# gatedriver_trafo_sma_compact_ACDC_SMD.net
KiCad netlist of a schematic drawn in EAGLE
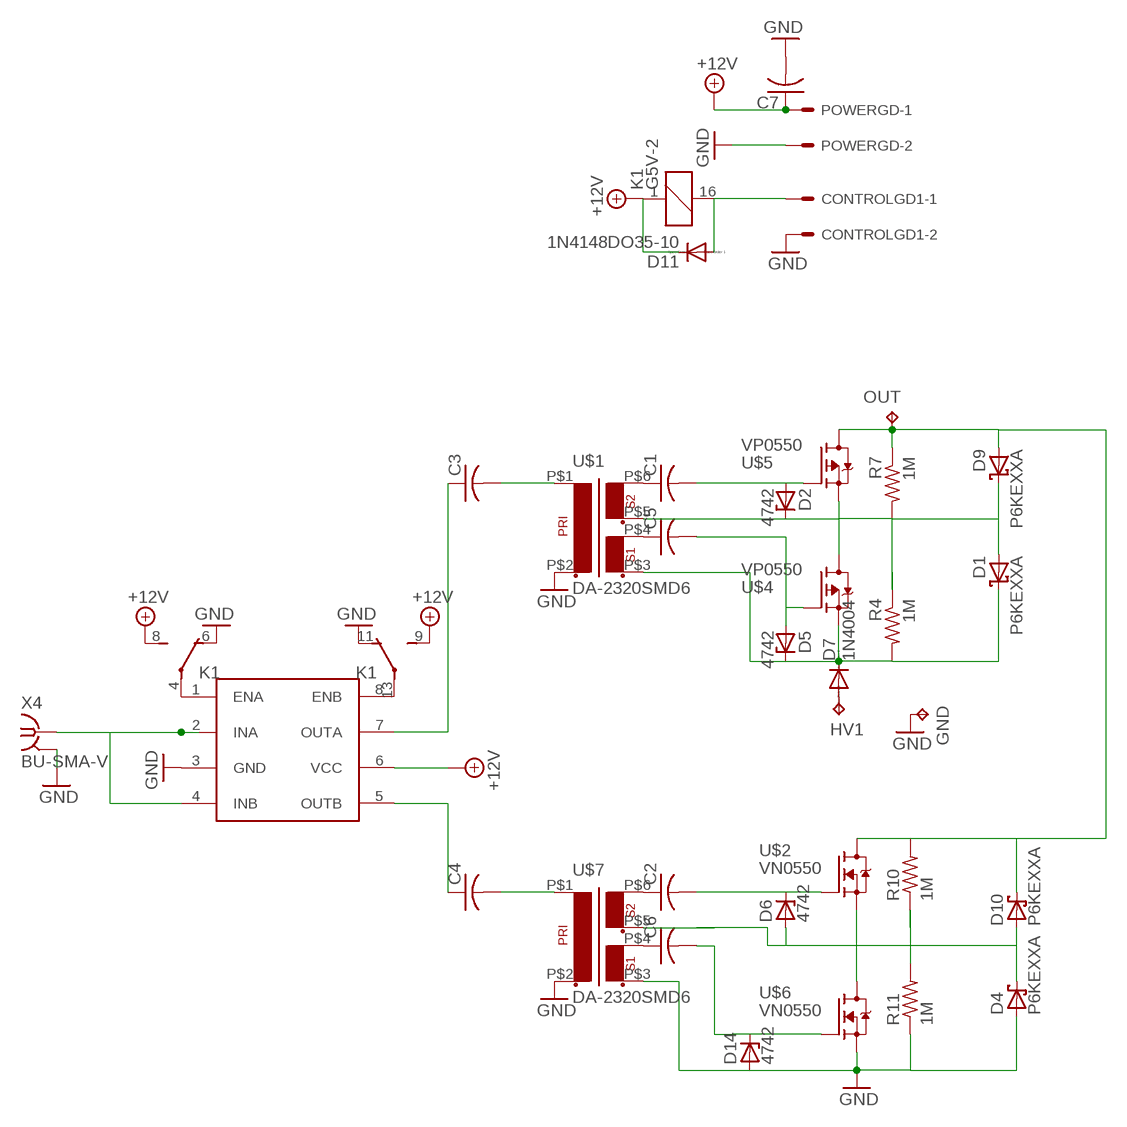
[diagram p0: schematic, sheet 1]

(export (version "E")
  (design (tool "Eeschema 10.0.6"))
  (components
    (comp (ref "C1")
      (value "C-US050-055X075")
      (footprint "eagle-import:C050-055X075")
      (libsource (lib "eagle-import") (part "resistor_C-US050-055X075"))
    )
    (comp (ref "C2")
      (value "C-US050-055X075")
      (footprint "eagle-import:C050-055X075")
      (libsource (lib "eagle-import") (part "resistor_C-US050-055X075"))
    )
    (comp (ref "C3")
      (value "C-US050-055X075")
      (footprint "eagle-import:C050-055X075")
      (libsource (lib "eagle-import") (part "resistor_C-US050-055X075"))
    )
    (comp (ref "C4")
      (value "C-US050-055X075")
      (footprint "eagle-import:C050-055X075")
      (libsource (lib "eagle-import") (part "resistor_C-US050-055X075"))
    )
    (comp (ref "C5")
      (value "C-US050-055X075")
      (footprint "eagle-import:C050-055X075")
      (libsource (lib "eagle-import") (part "resistor_C-US050-055X075"))
    )
    (comp (ref "C6")
      (value "C-US050-055X075")
      (footprint "eagle-import:C050-055X075")
      (libsource (lib "eagle-import") (part "resistor_C-US050-055X075"))
    )
    (comp (ref "C7")
      (value "C-US050-030X075")
      (footprint "eagle-import:C050-030X075")
      (libsource (lib "eagle-import") (part "C-US050-030X075"))
    )
    (comp (ref "CONTROLGD1")
      (value "KK-156-2")
      (footprint "eagle-import:KK-156-2")
      (libsource (lib "eagle-import") (part "KK-156-2"))
    )
    (comp (ref "D1")
      (value "P6KEXXA")
      (footprint "eagle-import:C1702-15")
      (libsource (lib "eagle-import") (part "P6KEXXA"))
    )
    (comp (ref "D2")
      (value "4742")
      (footprint "eagle-import:ZDIO-10")
      (libsource (lib "eagle-import") (part "ZENER-DIODEZD-10"))
    )
    (comp (ref "D4")
      (value "P6KEXXA")
      (footprint "eagle-import:C1702-15")
      (libsource (lib "eagle-import") (part "P6KEXXA"))
    )
    (comp (ref "D5")
      (value "4742")
      (footprint "eagle-import:ZDIO-10")
      (libsource (lib "eagle-import") (part "ZENER-DIODEZD-10"))
    )
    (comp (ref "D6")
      (value "4742")
      (footprint "eagle-import:ZDIO-10")
      (libsource (lib "eagle-import") (part "ZENER-DIODEZD-10"))
    )
    (comp (ref "D7")
      (value "1N4004")
      (footprint "eagle-import:DO41-10")
      (libsource (lib "eagle-import") (part "1N4004"))
    )
    (comp (ref "D9")
      (value "P6KEXXA")
      (footprint "eagle-import:C1702-15")
      (libsource (lib "eagle-import") (part "P6KEXXA"))
    )
    (comp (ref "D10")
      (value "P6KEXXA")
      (footprint "eagle-import:C1702-15")
      (libsource (lib "eagle-import") (part "P6KEXXA"))
    )
    (comp (ref "D11")
      (value "1N4148DO35-10")
      (footprint "eagle-import:DO35-10")
      (libsource (lib "eagle-import") (part "1N4148DO35-10"))
    )
    (comp (ref "D14")
      (value "4742")
      (footprint "eagle-import:ZDIO-10")
      (libsource (lib "eagle-import") (part "ZENER-DIODEZD-10"))
    )
    (comp (ref "GND")
      (value "TPPAD1-20Y")
      (footprint "eagle-import:P1-20Y")
      (libsource (lib "eagle-import") (part "TPPAD1-20Y"))
    )
    (comp (ref "HV1")
      (value "TPPAD1-20Y")
      (footprint "eagle-import:P1-20Y")
      (libsource (lib "eagle-import") (part "TPPAD1-20Y"))
    )
    (comp (ref "K1")
      (value "G5V-2")
      (footprint "eagle-import:G5V-2")
      (fields (field (name "MPN") "G5V-2 5DC"))
      (libsource (lib "eagle-import") (part "G5V-2"))
    )
    (comp (ref "OUT")
      (value "TPPAD1-20Y")
      (footprint "eagle-import:P1-20Y")
      (libsource (lib "eagle-import") (part "TPPAD1-20Y"))
    )
    (comp (ref "POWERGD")
      (value "KK-156-2")
      (footprint "eagle-import:KK-156-2")
      (libsource (lib "eagle-import") (part "KK-156-2"))
    )
    (comp (ref "R4")
      (value "1M")
      (footprint "eagle-import:0207_12")
      (libsource (lib "eagle-import") (part "R-US_0207/12"))
    )
    (comp (ref "R7")
      (value "1M")
      (footprint "eagle-import:0207_12")
      (libsource (lib "eagle-import") (part "R-US_0207/12"))
    )
    (comp (ref "R10")
      (value "1M")
      (footprint "eagle-import:0207_12")
      (libsource (lib "eagle-import") (part "R-US_0207/12"))
    )
    (comp (ref "R11")
      (value "1M")
      (footprint "eagle-import:0207_12")
      (libsource (lib "eagle-import") (part "R-US_0207/12"))
    )
    (comp (ref "U$1")
      (value "DA-2320SMD6")
      (footprint "eagle-import:SMD6")
      (libsource (lib "eagle-import") (part "DA-2320SMD6"))
    )
    (comp (ref "U$2")
      (value "VN0550")
      (footprint "eagle-import:TO92-")
      (libsource (lib "eagle-import") (part "VN0550"))
    )
    (comp (ref "U$3")
      (value "UCC27425")
      (footprint "eagle-import:DIL08")
      (libsource (lib "eagle-import") (part "UCC27425"))
    )
    (comp (ref "U$4")
      (value "VP0550")
      (footprint "eagle-import:TO92-")
      (libsource (lib "eagle-import") (part "VP0550"))
    )
    (comp (ref "U$5")
      (value "VP0550")
      (footprint "eagle-import:TO92-")
      (libsource (lib "eagle-import") (part "VP0550"))
    )
    (comp (ref "U$6")
      (value "VN0550")
      (footprint "eagle-import:TO92-")
      (libsource (lib "eagle-import") (part "VN0550"))
    )
    (comp (ref "U$7")
      (value "DA-2320SMD6")
      (footprint "eagle-import:SMD6")
      (libsource (lib "eagle-import") (part "DA-2320SMD6"))
    )
    (comp (ref "X4")
      (value "BU-SMA-V")
      (footprint "eagle-import:BU-SMA-V")
      (libsource (lib "eagle-import") (part "BU-SMA-V"))
    )
  )
  (nets
    (net (code "1") (name "+12V") (class "Default")
      (node (ref "C7") (pin "1") (pinfunction "1_1") (pintype "passive"))
      (node (ref "D11") (pin "C") (pinfunction "C_C") (pintype "passive"))
      (node (ref "K1") (pin "1") (pinfunction "1_1") (pintype "passive"))
      (node (ref "K1") (pin "8") (pinfunction "S_8") (pintype "passive"))
      (node (ref "K1") (pin "9") (pinfunction "S_9") (pintype "passive"))
      (node (ref "POWERGD") (pin "1") (pinfunction "S_1") (pintype "passive"))
      (node (ref "U$3") (pin "6") (pinfunction "VCC_6") (pintype "bidirectional"))
    )
    (net (code "2") (name "/N$25") (class "Default")
      (node (ref "C2") (pin "2") (pinfunction "2_2") (pintype "passive"))
      (node (ref "D6") (pin "C") (pinfunction "C_C") (pintype "passive"))
      (node (ref "U$2") (pin "2") (pinfunction "G_2") (pintype "passive"))
    )
    (net (code "3") (name "GND") (class "Default")
      (node (ref "C7") (pin "2") (pinfunction "2_2") (pintype "passive"))
      (node (ref "CONTROLGD1") (pin "2") (pinfunction "S_2") (pintype "passive"))
      (node (ref "D14") (pin "A") (pinfunction "A_A") (pintype "passive"))
      (node (ref "D4") (pin "A") (pinfunction "A_A") (pintype "passive"))
      (node (ref "GND") (pin "TP") (pinfunction "TP_TP") (pintype "input"))
      (node (ref "K1") (pin "11") (pinfunction "O_11") (pintype "passive"))
      (node (ref "K1") (pin "6") (pinfunction "O_6") (pintype "passive"))
      (node (ref "POWERGD") (pin "2") (pinfunction "S_2") (pintype "passive"))
      (node (ref "R11") (pin "1") (pinfunction "1_1") (pintype "passive"))
      (node (ref "U$1") (pin "P$2") (pinfunction "2_P$2") (pintype "passive"))
      (node (ref "U$3") (pin "3") (pinfunction "GND_3") (pintype "bidirectional"))
      (node (ref "U$6") (pin "3") (pinfunction "S_3") (pintype "passive"))
      (node (ref "U$7") (pin "P$2") (pinfunction "2_P$2") (pintype "passive"))
      (node (ref "U$7") (pin "P$3") (pinfunction "3_P$3") (pintype "passive"))
      (node (ref "X4") (pin "2") (pinfunction "2_2") (pintype "passive"))
      (node (ref "X4") (pin "3") (pinfunction "2_3") (pintype "passive"))
      (node (ref "X4") (pin "4") (pinfunction "2_4") (pintype "passive"))
      (node (ref "X4") (pin "5") (pinfunction "2_5") (pintype "passive"))
    )
    (net (code "4") (name "Net-(CONTROLGD1A-S)") (class "Default")
      (node (ref "CONTROLGD1") (pin "1") (pinfunction "S_1") (pintype "passive"))
      (node (ref "D11") (pin "A") (pinfunction "A_A") (pintype "passive"))
      (node (ref "K1") (pin "16") (pinfunction "2_16") (pintype "passive"))
    )
    (net (code "5") (name "Net-(D7-PadA)") (class "Default")
      (node (ref "D7") (pin "A") (pinfunction "A_A") (pintype "passive"))
      (node (ref "HV1") (pin "TP") (pinfunction "TP_TP") (pintype "input"))
    )
    (net (code "6") (name "Net-(K1A-P)") (class "Default")
      (node (ref "K1") (pin "4") (pinfunction "P_4") (pintype "passive"))
      (node (ref "U$3") (pin "1") (pinfunction "ENA_1") (pintype "bidirectional"))
    )
    (net (code "7") (name "Net-(K1B-P)") (class "Default")
      (node (ref "K1") (pin "13") (pinfunction "P_13") (pintype "passive"))
      (node (ref "U$3") (pin "8") (pinfunction "ENB_8") (pintype "bidirectional"))
    )
    (net (code "8") (name "Net-(U$1-1)") (class "Default")
      (node (ref "C3") (pin "2") (pinfunction "2_2") (pintype "passive"))
      (node (ref "U$1") (pin "P$1") (pinfunction "1_P$1") (pintype "passive"))
    )
    (net (code "9") (name "Net-(U$1-3)") (class "Default")
      (node (ref "D1") (pin "C") (pinfunction "C_C") (pintype "passive"))
      (node (ref "D5") (pin "C") (pinfunction "C_C") (pintype "passive"))
      (node (ref "D7") (pin "C") (pinfunction "C_C") (pintype "passive"))
      (node (ref "R4") (pin "2") (pinfunction "2_2") (pintype "passive"))
      (node (ref "U$1") (pin "P$3") (pinfunction "3_P$3") (pintype "passive"))
      (node (ref "U$4") (pin "3") (pinfunction "S_3") (pintype "passive"))
    )
    (net (code "10") (name "Net-(U$1-4)") (class "Default")
      (node (ref "C5") (pin "1") (pinfunction "1_1") (pintype "passive"))
      (node (ref "U$1") (pin "P$4") (pinfunction "4_P$4") (pintype "passive"))
    )
    (net (code "11") (name "Net-(U$1-5)") (class "Default")
      (node (ref "D1") (pin "A") (pinfunction "A_A") (pintype "passive"))
      (node (ref "D2") (pin "C") (pinfunction "C_C") (pintype "passive"))
      (node (ref "D9") (pin "C") (pinfunction "C_C") (pintype "passive"))
      (node (ref "R4") (pin "1") (pinfunction "1_1") (pintype "passive"))
      (node (ref "R7") (pin "2") (pinfunction "2_2") (pintype "passive"))
      (node (ref "U$1") (pin "P$5") (pinfunction "5_P$5") (pintype "passive"))
      (node (ref "U$4") (pin "1") (pinfunction "D_1") (pintype "passive"))
      (node (ref "U$5") (pin "3") (pinfunction "S_3") (pintype "passive"))
    )
    (net (code "12") (name "Net-(U$1-6)") (class "Default")
      (node (ref "C1") (pin "1") (pinfunction "1_1") (pintype "passive"))
      (node (ref "U$1") (pin "P$6") (pinfunction "6_P$6") (pintype "passive"))
    )
    (net (code "13") (name "Net-(U$2-D)") (class "Default")
      (node (ref "D10") (pin "C") (pinfunction "C_C") (pintype "passive"))
      (node (ref "D9") (pin "A") (pinfunction "A_A") (pintype "passive"))
      (node (ref "OUT") (pin "TP") (pinfunction "TP_TP") (pintype "input"))
      (node (ref "R10") (pin "2") (pinfunction "2_2") (pintype "passive"))
      (node (ref "R7") (pin "1") (pinfunction "1_1") (pintype "passive"))
      (node (ref "U$2") (pin "1") (pinfunction "D_1") (pintype "passive"))
      (node (ref "U$5") (pin "1") (pinfunction "D_1") (pintype "passive"))
    )
    (net (code "14") (name "Net-(U$2-S)") (class "Default")
      (node (ref "D10") (pin "A") (pinfunction "A_A") (pintype "passive"))
      (node (ref "D4") (pin "C") (pinfunction "C_C") (pintype "passive"))
      (node (ref "D6") (pin "A") (pinfunction "A_A") (pintype "passive"))
      (node (ref "R10") (pin "1") (pinfunction "1_1") (pintype "passive"))
      (node (ref "R11") (pin "2") (pinfunction "2_2") (pintype "passive"))
      (node (ref "U$2") (pin "3") (pinfunction "S_3") (pintype "passive"))
      (node (ref "U$6") (pin "1") (pinfunction "D_1") (pintype "passive"))
    )
    (net (code "15") (name "Net-(U$3-INA)") (class "Default")
      (node (ref "U$3") (pin "2") (pinfunction "INA_2") (pintype "bidirectional"))
      (node (ref "U$3") (pin "4") (pinfunction "INB_4") (pintype "bidirectional"))
      (node (ref "X4") (pin "1") (pinfunction "1_1") (pintype "passive"))
    )
    (net (code "16") (name "Net-(U$3-OUTA)") (class "Default")
      (node (ref "C3") (pin "1") (pinfunction "1_1") (pintype "passive"))
      (node (ref "U$3") (pin "7") (pinfunction "OUTA_7") (pintype "bidirectional"))
    )
    (net (code "17") (name "Net-(U$3-OUTB)") (class "Default")
      (node (ref "C4") (pin "1") (pinfunction "1_1") (pintype "passive"))
      (node (ref "U$3") (pin "5") (pinfunction "OUTB_5") (pintype "bidirectional"))
    )
    (net (code "18") (name "Net-(U$4-G)") (class "Default")
      (node (ref "C5") (pin "2") (pinfunction "2_2") (pintype "passive"))
      (node (ref "D5") (pin "A") (pinfunction "A_A") (pintype "passive"))
      (node (ref "U$4") (pin "2") (pinfunction "G_2") (pintype "passive"))
    )
    (net (code "19") (name "Net-(U$5-G)") (class "Default")
      (node (ref "C1") (pin "2") (pinfunction "2_2") (pintype "passive"))
      (node (ref "D2") (pin "A") (pinfunction "A_A") (pintype "passive"))
      (node (ref "U$5") (pin "2") (pinfunction "G_2") (pintype "passive"))
    )
    (net (code "20") (name "Net-(U$6-G)") (class "Default")
      (node (ref "C6") (pin "2") (pinfunction "2_2") (pintype "passive"))
      (node (ref "D14") (pin "C") (pinfunction "C_C") (pintype "passive"))
      (node (ref "U$6") (pin "2") (pinfunction "G_2") (pintype "passive"))
    )
    (net (code "21") (name "Net-(U$7-1)") (class "Default")
      (node (ref "C4") (pin "2") (pinfunction "2_2") (pintype "passive"))
      (node (ref "U$7") (pin "P$1") (pinfunction "1_P$1") (pintype "passive"))
    )
    (net (code "22") (name "Net-(U$7-4)") (class "Default")
      (node (ref "C6") (pin "1") (pinfunction "1_1") (pintype "passive"))
      (node (ref "U$7") (pin "P$4") (pinfunction "4_P$4") (pintype "passive"))
    )
    (net (code "23") (name "Net-(U$7-6)") (class "Default")
      (node (ref "C2") (pin "1") (pinfunction "1_1") (pintype "passive"))
      (node (ref "U$7") (pin "P$6") (pinfunction "6_P$6") (pintype "passive"))
    )
    (net (code "24") (name "unconnected-(U$7-5-PadP$5)") (class "Default")
      (node (ref "U$7") (pin "P$5") (pinfunction "5_P$5") (pintype "passive"))
    )
  )
)
